# 12_-_IMX6_DDR3.net
KiCad netlist of a schematic drawn in Altium Designer
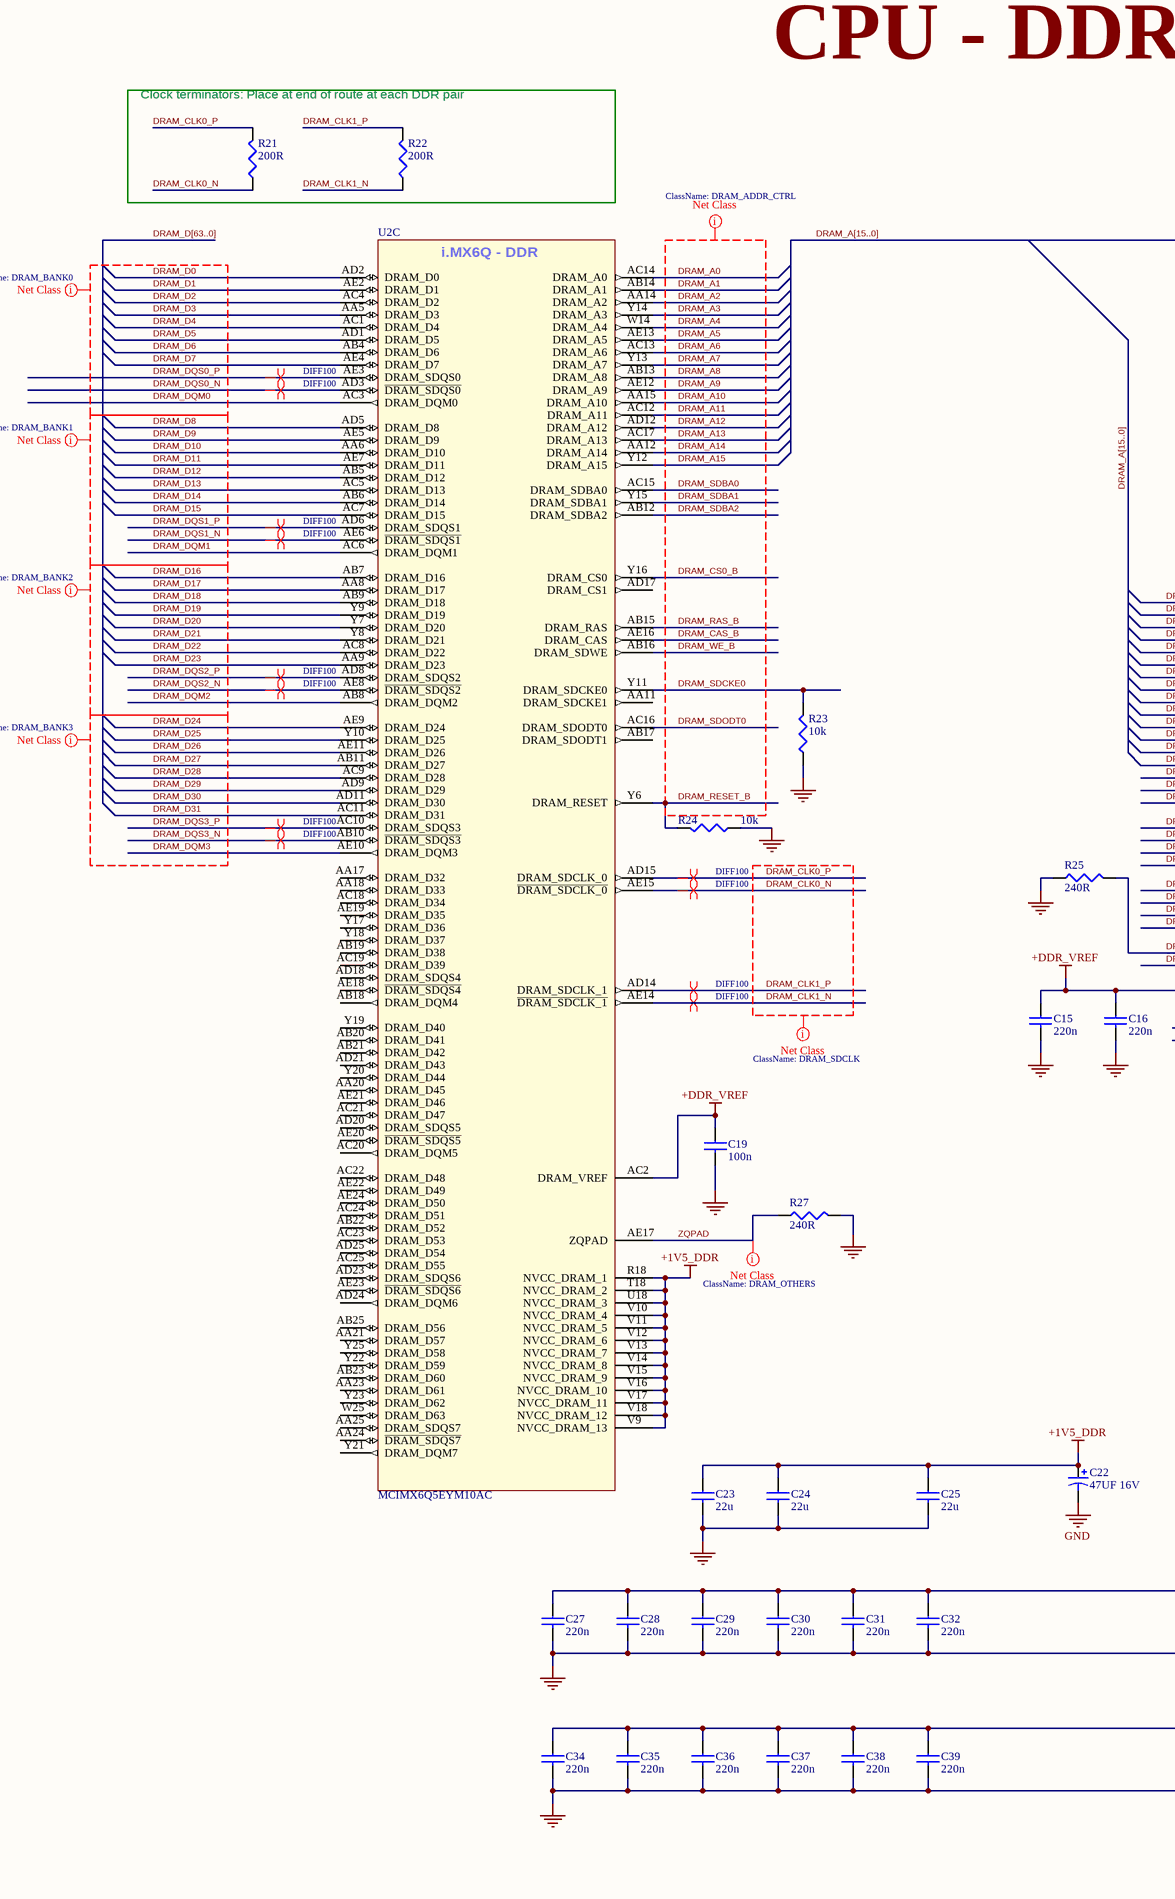
[diagram p0: [12] - IMX6_DDR3.SchDoc, left]
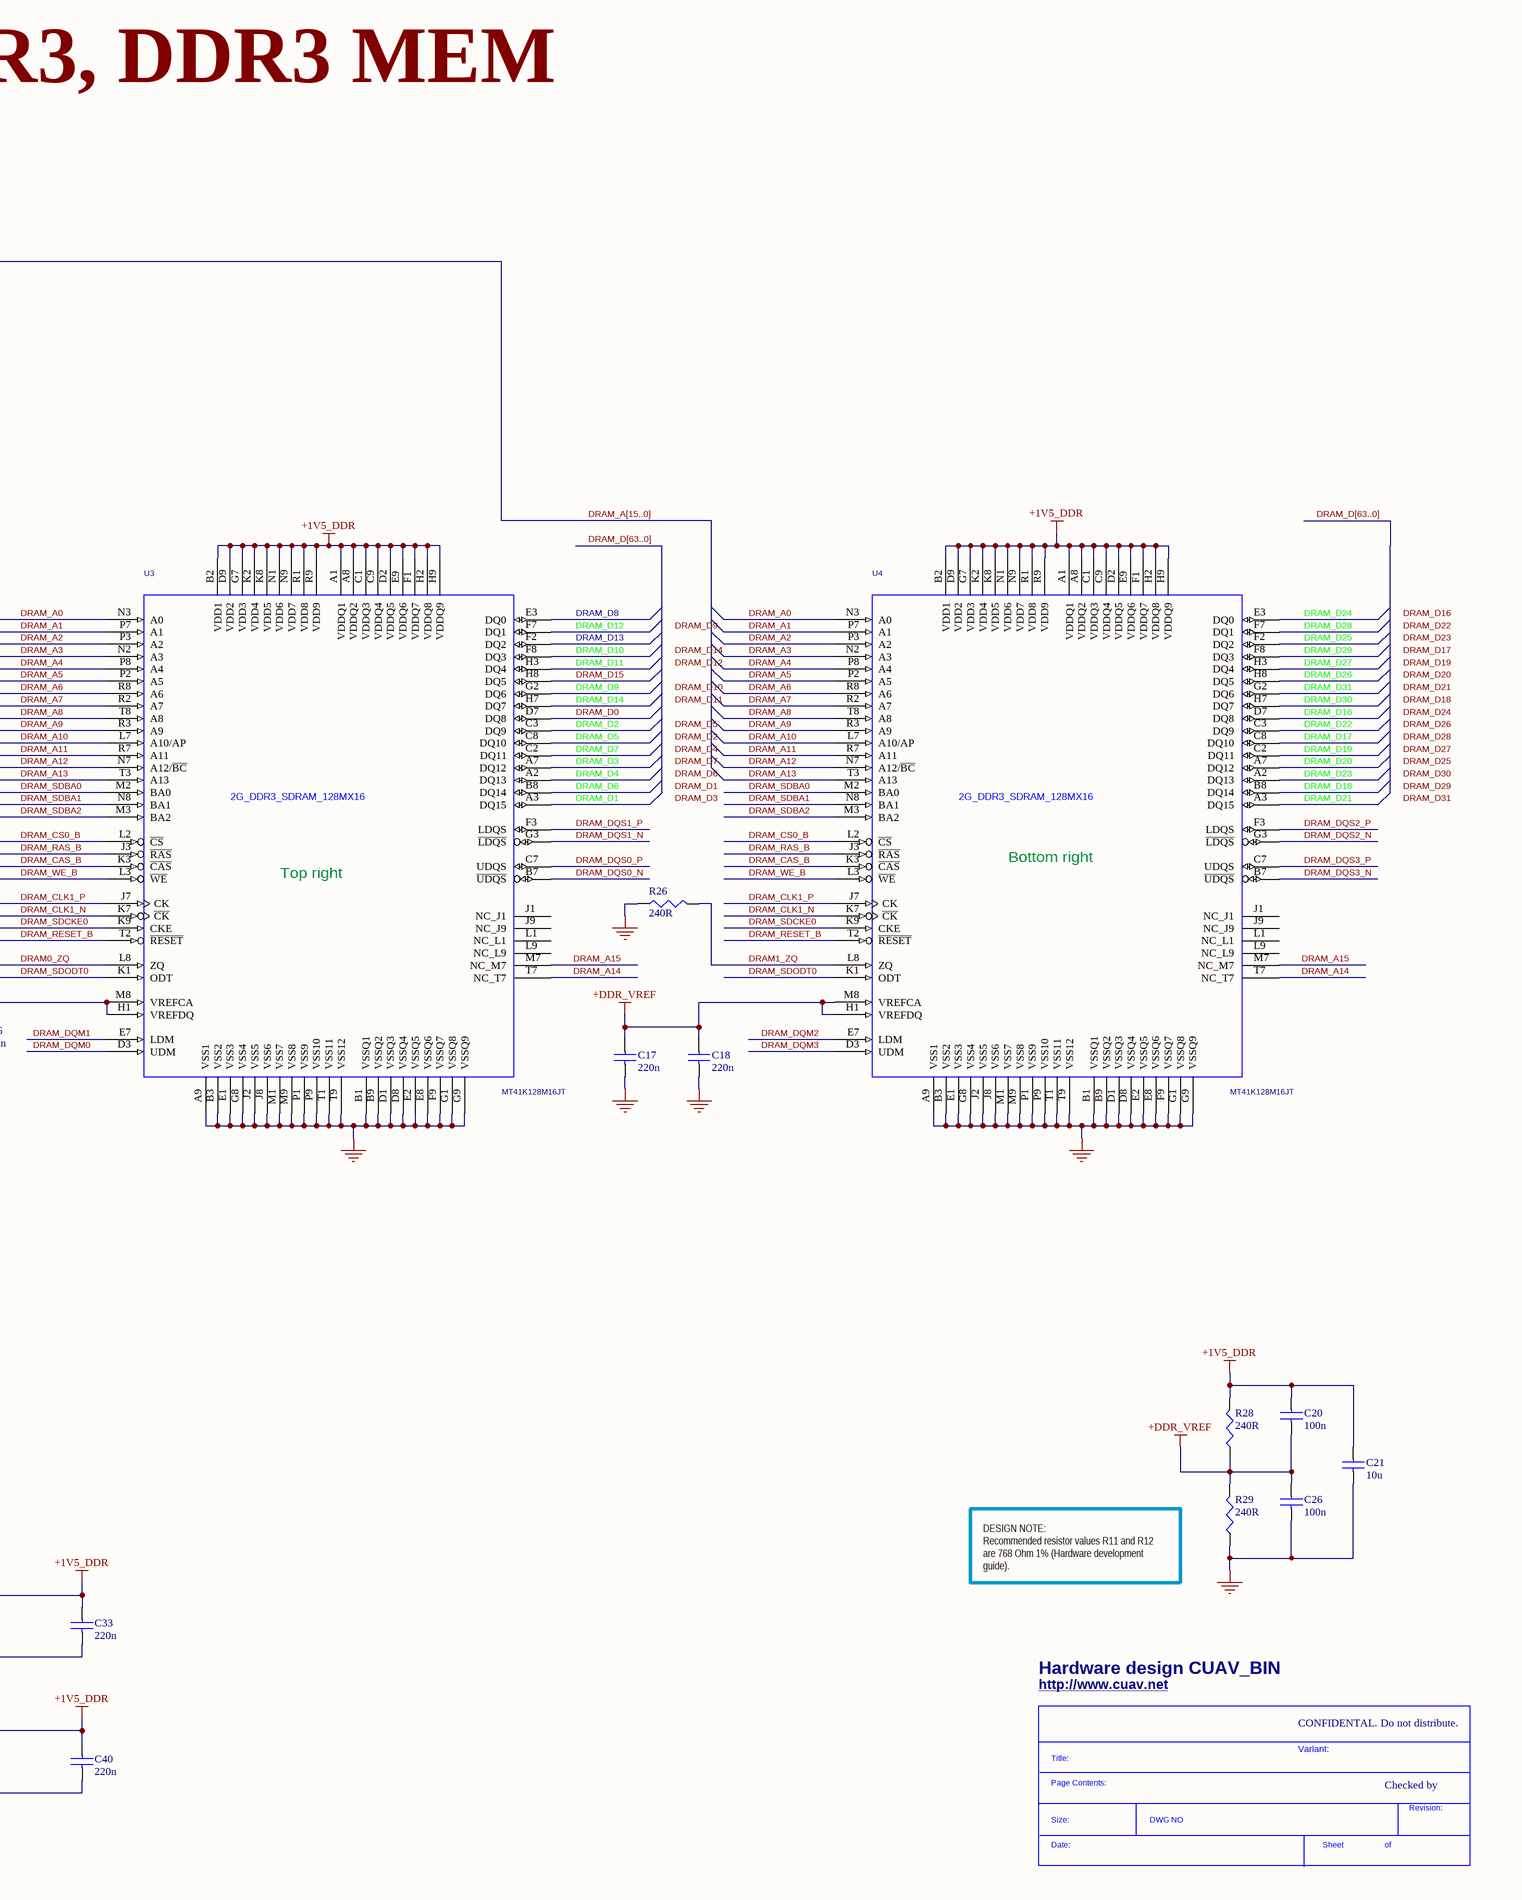
[diagram p1: [12] - IMX6_DDR3.SchDoc, right]

(export (version "E")
  (design (tool "Eeschema 10.0.6"))
  (components
    (comp (ref "*") (value "SDTitleBlock") (libsource (lib "*") (part "SDTitleBlock")))
    (comp (ref "C15")
      (value "220n")
      (footprint "0402CAP")
      (description "CAP CER .22UF 25V X5R 20% 0402")
      (fields
        (field (name "MANUFACTURER") "TDK Corporation")
        (field (name "MANUFACTURER PART NUMBER") "C1005X5R1E224M")
      )
      (libsource (lib "Integrated_Library_RF_FEB_2012") (part "C1005X5R1E224M"))
    )
    (comp (ref "C16")
      (value "220n")
      (footprint "0402CAP")
      (description "CAP CER .22UF 25V X5R 20% 0402")
      (fields
        (field (name "MANUFACTURER") "TDK Corporation")
        (field (name "MANUFACTURER PART NUMBER") "C1005X5R1E224M")
      )
      (libsource (lib "Integrated_Library_RF_FEB_2012") (part "C1005X5R1E224M"))
    )
    (comp (ref "C17")
      (value "220n")
      (footprint "0402CAP")
      (description "CAP CER .22UF 25V X5R 20% 0402")
      (fields
        (field (name "MANUFACTURER") "TDK Corporation")
        (field (name "MANUFACTURER PART NUMBER") "C1005X5R1E224M")
      )
      (libsource (lib "Integrated_Library_RF_FEB_2012") (part "C1005X5R1E224M"))
    )
    (comp (ref "C18")
      (value "220n")
      (footprint "0402CAP")
      (description "CAP CER .22UF 25V X5R 20% 0402")
      (fields
        (field (name "MANUFACTURER") "TDK Corporation")
        (field (name "MANUFACTURER PART NUMBER") "C1005X5R1E224M")
      )
      (libsource (lib "Integrated_Library_RF_FEB_2012") (part "C1005X5R1E224M"))
    )
    (comp (ref "C19")
      (value "100n")
      (footprint "C0402")
      (description "CAP CER .10UF 50V X5R 10% 0402")
      (fields
        (field (name "MANUFACTURER") "TDK Corporation")
        (field (name "MANUFACTURER PART NUMBER") "C1005X5R1H104K")
      )
      (libsource (lib "Integrated_Library_RF_FEB_2012") (part "C1005X5R1H104K"))
    )
    (comp (ref "C20")
      (value "100n")
      (footprint "0402CAP")
      (description "CAP CER .10UF 50V X5R 10% 0402")
      (fields
        (field (name "MANUFACTURER") "TDK Corporation")
        (field (name "MANUFACTURER PART NUMBER") "C1005X5R1H104K")
      )
      (libsource (lib "Integrated_Library_RF_FEB_2012") (part "C1005X5R1H104K"))
    )
    (comp (ref "C21")
      (value "10u")
      (footprint "C0603")
      (description "CAP CER 10UF 6.3V X5R 20% 0603")
      (fields
        (field (name "MANUFACTURER") "TDK Corporation")
        (field (name "MANUFACTURER PART NUMBER") "C1608X5R0J106M")
      )
      (libsource (lib "Integrated_Library_RF_FEB_2012") (part "C1608X5R0J106M"))
    )
    (comp (ref "C22")
      (value "47UF 16V")
      (footprint "7343CAP")
      (description "Polarized Capacitor (Radial)")
      (fields (field (name "PUBLISHER") "Altium Limited"))
      (libsource (lib "Miscellaneous Devices") (part "Cap Pol1"))
    )
    (comp (ref "C23")
      (value "22u")
      (footprint "C0603")
      (description "CAP CER 22UF 4V 20% X5R 0603")
      (fields
        (field (name "MANUFACTURER") "Murata Electronics North America")
        (field (name "MANUFACTURER PART NUMBER") "GRM188R60G226MEA0L")
        (field (name ".CHECKED PCB") "RF, used by MM")
        (field (name ".CHECKED SCH") "MM, checked by RF")
        (field (name ".CREATOR") "MM")
      )
      (libsource (lib "Schlib_RF") (part "GRM188R60G226MEA0L"))
    )
    (comp (ref "C24")
      (value "22u")
      (footprint "C0603")
      (description "CAP CER 22UF 4V 20% X5R 0603")
      (fields
        (field (name "MANUFACTURER") "Murata Electronics North America")
        (field (name "MANUFACTURER PART NUMBER") "GRM188R60G226MEA0L")
        (field (name ".CHECKED PCB") "RF, used by MM")
        (field (name ".CHECKED SCH") "MM, checked by RF")
        (field (name ".CREATOR") "MM")
      )
      (libsource (lib "Schlib_RF") (part "GRM188R60G226MEA0L"))
    )
    (comp (ref "C25")
      (value "22u")
      (footprint "C0603")
      (description "CAP CER 22UF 4V 20% X5R 0603")
      (fields
        (field (name "MANUFACTURER") "Murata Electronics North America")
        (field (name "MANUFACTURER PART NUMBER") "GRM188R60G226MEA0L")
        (field (name ".CHECKED PCB") "RF, used by MM")
        (field (name ".CHECKED SCH") "MM, checked by RF")
        (field (name ".CREATOR") "MM")
      )
      (libsource (lib "Schlib_RF") (part "GRM188R60G226MEA0L"))
    )
    (comp (ref "C26")
      (value "100n")
      (footprint "0402CAP")
      (description "CAP CER .10UF 50V X5R 10% 0402")
      (fields
        (field (name "MANUFACTURER") "TDK Corporation")
        (field (name "MANUFACTURER PART NUMBER") "C1005X5R1H104K")
      )
      (libsource (lib "Integrated_Library_RF_FEB_2012") (part "C1005X5R1H104K"))
    )
    (comp (ref "C27")
      (value "220n")
      (footprint "0402CAP")
      (description "CAP CER .22UF 25V X5R 20% 0402")
      (fields
        (field (name "MANUFACTURER") "TDK Corporation")
        (field (name "MANUFACTURER PART NUMBER") "C1005X5R1E224M")
      )
      (libsource (lib "Integrated_Library_RF_FEB_2012") (part "C1005X5R1E224M"))
    )
    (comp (ref "C28")
      (value "220n")
      (footprint "0402CAP")
      (description "CAP CER .22UF 25V X5R 20% 0402")
      (fields
        (field (name "MANUFACTURER") "TDK Corporation")
        (field (name "MANUFACTURER PART NUMBER") "C1005X5R1E224M")
      )
      (libsource (lib "Integrated_Library_RF_FEB_2012") (part "C1005X5R1E224M"))
    )
    (comp (ref "C29")
      (value "220n")
      (footprint "0402CAP")
      (description "CAP CER .22UF 25V X5R 20% 0402")
      (fields
        (field (name "MANUFACTURER") "TDK Corporation")
        (field (name "MANUFACTURER PART NUMBER") "C1005X5R1E224M")
      )
      (libsource (lib "Integrated_Library_RF_FEB_2012") (part "C1005X5R1E224M"))
    )
    (comp (ref "C30")
      (value "220n")
      (footprint "0402CAP")
      (description "CAP CER .22UF 25V X5R 20% 0402")
      (fields
        (field (name "MANUFACTURER") "TDK Corporation")
        (field (name "MANUFACTURER PART NUMBER") "C1005X5R1E224M")
      )
      (libsource (lib "Integrated_Library_RF_FEB_2012") (part "C1005X5R1E224M"))
    )
    (comp (ref "C31")
      (value "220n")
      (footprint "0402CAP")
      (description "CAP CER .22UF 25V X5R 20% 0402")
      (fields
        (field (name "MANUFACTURER") "TDK Corporation")
        (field (name "MANUFACTURER PART NUMBER") "C1005X5R1E224M")
      )
      (libsource (lib "Integrated_Library_RF_FEB_2012") (part "C1005X5R1E224M"))
    )
    (comp (ref "C32")
      (value "220n")
      (footprint "0402CAP")
      (description "CAP CER .22UF 25V X5R 20% 0402")
      (fields
        (field (name "MANUFACTURER") "TDK Corporation")
        (field (name "MANUFACTURER PART NUMBER") "C1005X5R1E224M")
      )
      (libsource (lib "Integrated_Library_RF_FEB_2012") (part "C1005X5R1E224M"))
    )
    (comp (ref "C33")
      (value "220n")
      (footprint "0402CAP")
      (description "CAP CER .22UF 25V X5R 20% 0402")
      (fields
        (field (name "MANUFACTURER") "TDK Corporation")
        (field (name "MANUFACTURER PART NUMBER") "C1005X5R1E224M")
      )
      (libsource (lib "Integrated_Library_RF_FEB_2012") (part "C1005X5R1E224M"))
    )
    (comp (ref "C34")
      (value "220n")
      (footprint "0402CAP")
      (description "CAP CER .22UF 25V X5R 20% 0402")
      (fields
        (field (name "MANUFACTURER") "TDK Corporation")
        (field (name "MANUFACTURER PART NUMBER") "C1005X5R1E224M")
      )
      (libsource (lib "Integrated_Library_RF_FEB_2012") (part "C1005X5R1E224M"))
    )
    (comp (ref "C35")
      (value "220n")
      (footprint "0402CAP")
      (description "CAP CER .22UF 25V X5R 20% 0402")
      (fields
        (field (name "MANUFACTURER") "TDK Corporation")
        (field (name "MANUFACTURER PART NUMBER") "C1005X5R1E224M")
      )
      (libsource (lib "Integrated_Library_RF_FEB_2012") (part "C1005X5R1E224M"))
    )
    (comp (ref "C36")
      (value "220n")
      (footprint "0402CAP")
      (description "CAP CER .22UF 25V X5R 20% 0402")
      (fields
        (field (name "MANUFACTURER") "TDK Corporation")
        (field (name "MANUFACTURER PART NUMBER") "C1005X5R1E224M")
      )
      (libsource (lib "Integrated_Library_RF_FEB_2012") (part "C1005X5R1E224M"))
    )
    (comp (ref "C37")
      (value "220n")
      (footprint "0402CAP")
      (description "CAP CER .22UF 25V X5R 20% 0402")
      (fields
        (field (name "MANUFACTURER") "TDK Corporation")
        (field (name "MANUFACTURER PART NUMBER") "C1005X5R1E224M")
      )
      (libsource (lib "Integrated_Library_RF_FEB_2012") (part "C1005X5R1E224M"))
    )
    (comp (ref "C38")
      (value "220n")
      (footprint "0402CAP")
      (description "CAP CER .22UF 25V X5R 20% 0402")
      (fields
        (field (name "MANUFACTURER") "TDK Corporation")
        (field (name "MANUFACTURER PART NUMBER") "C1005X5R1E224M")
      )
      (libsource (lib "Integrated_Library_RF_FEB_2012") (part "C1005X5R1E224M"))
    )
    (comp (ref "C39")
      (value "220n")
      (footprint "0402CAP")
      (description "CAP CER .22UF 25V X5R 20% 0402")
      (fields
        (field (name "MANUFACTURER") "TDK Corporation")
        (field (name "MANUFACTURER PART NUMBER") "C1005X5R1E224M")
      )
      (libsource (lib "Integrated_Library_RF_FEB_2012") (part "C1005X5R1E224M"))
    )
    (comp (ref "C40")
      (value "220n")
      (footprint "0402CAP")
      (description "CAP CER .22UF 25V X5R 20% 0402")
      (fields
        (field (name "MANUFACTURER") "TDK Corporation")
        (field (name "MANUFACTURER PART NUMBER") "C1005X5R1E224M")
      )
      (libsource (lib "Integrated_Library_RF_FEB_2012") (part "C1005X5R1E224M"))
    )
    (comp (ref "R21")
      (value "200R")
      (footprint "R0402")
      (description "RES 200 OHM 1/16W 1% 0402 SMD")
      (fields
        (field (name "MANUFACTURER") "Vishay Dale")
        (field (name "MANUFACTURER PART NUMBER") "CRCW0402200RFKED")
        (field (name ".CHECKED PCB") "RF, used by MM")
        (field (name ".CHECKED SCH") "MM, checked by RF")
        (field (name ".CREATOR") "MM")
      )
      (libsource (lib "Schlib_RF") (part "CRCW0402200RFKED"))
    )
    (comp (ref "R22")
      (value "200R")
      (footprint "R0402")
      (description "RES 200 OHM 1/16W 1% 0402 SMD")
      (fields
        (field (name "MANUFACTURER") "Vishay Dale")
        (field (name "MANUFACTURER PART NUMBER") "CRCW0402200RFKED")
        (field (name ".CHECKED PCB") "RF, used by MM")
        (field (name ".CHECKED SCH") "MM, checked by RF")
        (field (name ".CREATOR") "MM")
      )
      (libsource (lib "Schlib_RF") (part "CRCW0402200RFKED"))
    )
    (comp (ref "R23")
      (value "10k")
      (footprint "R0402")
      (description "RES 10.0K OHM 1/16W 1% 0402 SMD")
      (fields
        (field (name "MANUFACTURER") "Yageo")
        (field (name "MANUFACTURER PART NUMBER") "RC0402FR-0710KL")
      )
      (libsource (lib "Integrated_Library_RF_FEB_2012") (part "RC0402FR-0710KL"))
    )
    (comp (ref "R24")
      (value "10k")
      (footprint "R0402")
      (description "RES 10.0K OHM 1/16W 1% 0402 SMD")
      (fields
        (field (name "MANUFACTURER") "Yageo")
        (field (name "MANUFACTURER PART NUMBER") "RC0402FR-0710KL")
      )
      (libsource (lib "Integrated_Library_RF_FEB_2012") (part "RC0402FR-0710KL"))
    )
    (comp (ref "R25")
      (value "240R")
      (footprint "R0402")
      (description "RES TF 240 OHM 1% 0.0625W 0402")
      (fields
        (field (name "MANUFACTURER") "Stackpole Electronics Inc")
        (field (name "MANUFACTURER PART NUMBER") "RMCF0402FT240R")
      )
      (libsource (lib "Integrated_Library_RF_FEB_2012") (part "RMCF0402FT240R"))
    )
    (comp (ref "R26")
      (value "240R")
      (footprint "R0402")
      (description "RES TF 240 OHM 1% 0.0625W 0402")
      (fields
        (field (name "MANUFACTURER") "Stackpole Electronics Inc")
        (field (name "MANUFACTURER PART NUMBER") "RMCF0402FT240R")
      )
      (libsource (lib "Integrated_Library_RF_FEB_2012") (part "RMCF0402FT240R"))
    )
    (comp (ref "R27")
      (value "240R")
      (footprint "R0402")
      (description "RES TF 240 OHM 1% 0.0625W 0402")
      (fields
        (field (name "MANUFACTURER") "Stackpole Electronics Inc")
        (field (name "MANUFACTURER PART NUMBER") "RMCF0402FT240R")
      )
      (libsource (lib "Integrated_Library_RF_FEB_2012") (part "RMCF0402FT240R"))
    )
    (comp (ref "R28")
      (value "240R")
      (footprint "R0402")
      (description "RES TF 240 OHM 1% 0.0625W 0402")
      (fields
        (field (name "MANUFACTURER") "Stackpole Electronics Inc")
        (field (name "MANUFACTURER PART NUMBER") "RMCF0402FT240R")
      )
      (libsource (lib "Integrated_Library_RF_FEB_2012") (part "RMCF0402FT240R"))
    )
    (comp (ref "R29")
      (value "240R")
      (footprint "R0402")
      (description "RES TF 240 OHM 1% 0.0625W 0402")
      (fields
        (field (name "MANUFACTURER") "Stackpole Electronics Inc")
        (field (name "MANUFACTURER PART NUMBER") "RMCF0402FT240R")
      )
      (libsource (lib "Integrated_Library_RF_FEB_2012") (part "RMCF0402FT240R"))
    )
    (comp (ref "U2")
      (value "MCIMX6Q5EYM10AC")
      (footprint "PBGA624")
      (description "IC MCU 32BIT ARM QUAD 624FCBGA")
      (fields
        (field (name "MANUFACTURER") "Freescale Semiconductor")
        (field (name ".CREATOR") "MM")
        (field (name ".CHECKED PCB") "MM, checked by RF")
        (field (name ".CHECKED SCH") "MM")
      )
      (libsource (lib "Schlib_RF") (part "MCIMX6Q5EYM10AC"))
    )
    (comp (ref "U3")
      (value "MT41K128M16JT")
      (footprint "96_FPGA_DD3")
      (description "IC MEM DDR3 SDRAM 2Gb 128MX16 1.35V FBGA96")
      (libsource (lib "*") (part "2G_DDR3_SDRAM_128MX16_96P"))
    )
    (comp (ref "U4")
      (value "MT41K128M16JT")
      (footprint "96_FPGA_DD3")
      (description "IC MEM DDR3 SDRAM 2Gb 128MX16 1.35V FBGA96")
      (libsource (lib "*") (part "2G_DDR3_SDRAM_128MX16_96P"))
    )
  )
  (nets
    (net (code "33") (name "+1V5_DDR") (class "Default")
      (node (ref "C20") (pin "1") (pinfunction "1_1") (pintype "passive"))
      (node (ref "C21") (pin "1") (pinfunction "1_1") (pintype "passive"))
      (node (ref "C22") (pin "A") (pinfunction "1_A") (pintype "passive"))
      (node (ref "C23") (pin "1") (pinfunction "1_1") (pintype "passive"))
      (node (ref "C24") (pin "1") (pinfunction "1_1") (pintype "passive"))
      (node (ref "C25") (pin "1") (pinfunction "1_1") (pintype "passive"))
      (node (ref "C27") (pin "1") (pinfunction "1_1") (pintype "passive"))
      (node (ref "C28") (pin "1") (pinfunction "1_1") (pintype "passive"))
      (node (ref "C29") (pin "1") (pinfunction "1_1") (pintype "passive"))
      (node (ref "C30") (pin "1") (pinfunction "1_1") (pintype "passive"))
      (node (ref "C31") (pin "1") (pinfunction "1_1") (pintype "passive"))
      (node (ref "C32") (pin "1") (pinfunction "1_1") (pintype "passive"))
      (node (ref "C33") (pin "1") (pinfunction "1_1") (pintype "passive"))
      (node (ref "C34") (pin "1") (pinfunction "1_1") (pintype "passive"))
      (node (ref "C35") (pin "1") (pinfunction "1_1") (pintype "passive"))
      (node (ref "C36") (pin "1") (pinfunction "1_1") (pintype "passive"))
      (node (ref "C37") (pin "1") (pinfunction "1_1") (pintype "passive"))
      (node (ref "C38") (pin "1") (pinfunction "1_1") (pintype "passive"))
      (node (ref "C39") (pin "1") (pinfunction "1_1") (pintype "passive"))
      (node (ref "C40") (pin "1") (pinfunction "1_1") (pintype "passive"))
      (node (ref "R28") (pin "2") (pinfunction "2_2") (pintype "passive"))
      (node (ref "U2") (pin "R18") (pinfunction "NVCC_DRAM_1_R18") (pintype "power_in"))
      (node (ref "U2") (pin "T18") (pinfunction "NVCC_DRAM_2_T18") (pintype "power_in"))
      (node (ref "U2") (pin "U18") (pinfunction "NVCC_DRAM_3_U18") (pintype "power_in"))
      (node (ref "U2") (pin "V10") (pinfunction "NVCC_DRAM_4_V10") (pintype "power_in"))
      (node (ref "U2") (pin "V11") (pinfunction "NVCC_DRAM_5_V11") (pintype "power_in"))
      (node (ref "U2") (pin "V12") (pinfunction "NVCC_DRAM_6_V12") (pintype "power_in"))
      (node (ref "U2") (pin "V13") (pinfunction "NVCC_DRAM_7_V13") (pintype "power_in"))
      (node (ref "U2") (pin "V14") (pinfunction "NVCC_DRAM_8_V14") (pintype "power_in"))
      (node (ref "U2") (pin "V15") (pinfunction "NVCC_DRAM_9_V15") (pintype "power_in"))
      (node (ref "U2") (pin "V16") (pinfunction "NVCC_DRAM_10_V16") (pintype "power_in"))
      (node (ref "U2") (pin "V17") (pinfunction "NVCC_DRAM_11_V17") (pintype "power_in"))
      (node (ref "U2") (pin "V18") (pinfunction "NVCC_DRAM_12_V18") (pintype "power_in"))
      (node (ref "U2") (pin "V9") (pinfunction "NVCC_DRAM_13_V9") (pintype "power_in"))
      (node (ref "U3") (pin "A1") (pinfunction "VDDQ1_A1") (pintype "power_in"))
      (node (ref "U3") (pin "A8") (pinfunction "VDDQ2_A8") (pintype "power_in"))
      (node (ref "U3") (pin "B2") (pinfunction "VDD1_B2") (pintype "power_in"))
      (node (ref "U3") (pin "C1") (pinfunction "VDDQ3_C1") (pintype "power_in"))
      (node (ref "U3") (pin "C9") (pinfunction "VDDQ4_C9") (pintype "power_in"))
      (node (ref "U3") (pin "D2") (pinfunction "VDDQ5_D2") (pintype "power_in"))
      (node (ref "U3") (pin "D9") (pinfunction "VDD2_D9") (pintype "power_in"))
      (node (ref "U3") (pin "E9") (pinfunction "VDDQ6_E9") (pintype "power_in"))
      (node (ref "U3") (pin "F1") (pinfunction "VDDQ7_F1") (pintype "power_in"))
      (node (ref "U3") (pin "G7") (pinfunction "VDD3_G7") (pintype "power_in"))
      (node (ref "U3") (pin "H2") (pinfunction "VDDQ8_H2") (pintype "power_in"))
      (node (ref "U3") (pin "H9") (pinfunction "VDDQ9_H9") (pintype "power_in"))
      (node (ref "U3") (pin "K2") (pinfunction "VDD4_K2") (pintype "power_in"))
      (node (ref "U3") (pin "K8") (pinfunction "VDD5_K8") (pintype "power_in"))
      (node (ref "U3") (pin "N1") (pinfunction "VDD6_N1") (pintype "power_in"))
      (node (ref "U3") (pin "N9") (pinfunction "VDD7_N9") (pintype "power_in"))
      (node (ref "U3") (pin "R1") (pinfunction "VDD8_R1") (pintype "power_in"))
      (node (ref "U3") (pin "R9") (pinfunction "VDD9_R9") (pintype "power_in"))
      (node (ref "U4") (pin "A1") (pinfunction "VDDQ1_A1") (pintype "power_in"))
      (node (ref "U4") (pin "A8") (pinfunction "VDDQ2_A8") (pintype "power_in"))
      (node (ref "U4") (pin "B2") (pinfunction "VDD1_B2") (pintype "power_in"))
      (node (ref "U4") (pin "C1") (pinfunction "VDDQ3_C1") (pintype "power_in"))
      (node (ref "U4") (pin "C9") (pinfunction "VDDQ4_C9") (pintype "power_in"))
      (node (ref "U4") (pin "D2") (pinfunction "VDDQ5_D2") (pintype "power_in"))
      (node (ref "U4") (pin "D9") (pinfunction "VDD2_D9") (pintype "power_in"))
      (node (ref "U4") (pin "E9") (pinfunction "VDDQ6_E9") (pintype "power_in"))
      (node (ref "U4") (pin "F1") (pinfunction "VDDQ7_F1") (pintype "power_in"))
      (node (ref "U4") (pin "G7") (pinfunction "VDD3_G7") (pintype "power_in"))
      (node (ref "U4") (pin "H2") (pinfunction "VDDQ8_H2") (pintype "power_in"))
      (node (ref "U4") (pin "H9") (pinfunction "VDDQ9_H9") (pintype "power_in"))
      (node (ref "U4") (pin "K2") (pinfunction "VDD4_K2") (pintype "power_in"))
      (node (ref "U4") (pin "K8") (pinfunction "VDD5_K8") (pintype "power_in"))
      (node (ref "U4") (pin "N1") (pinfunction "VDD6_N1") (pintype "power_in"))
      (node (ref "U4") (pin "N9") (pinfunction "VDD7_N9") (pintype "power_in"))
      (node (ref "U4") (pin "R1") (pinfunction "VDD8_R1") (pintype "power_in"))
      (node (ref "U4") (pin "R9") (pinfunction "VDD9_R9") (pintype "power_in"))
    )
    (net (code "34") (name "+DDR_VREF") (class "Default")
      (node (ref "C15") (pin "1") (pinfunction "1_1") (pintype "passive"))
      (node (ref "C16") (pin "1") (pinfunction "1_1") (pintype "passive"))
      (node (ref "C17") (pin "1") (pinfunction "1_1") (pintype "passive"))
      (node (ref "C18") (pin "1") (pinfunction "1_1") (pintype "passive"))
      (node (ref "C19") (pin "1") (pinfunction "1_1") (pintype "passive"))
      (node (ref "C20") (pin "2") (pinfunction "2_2") (pintype "passive"))
      (node (ref "C26") (pin "1") (pinfunction "1_1") (pintype "passive"))
      (node (ref "R28") (pin "1") (pinfunction "1_1") (pintype "passive"))
      (node (ref "R29") (pin "2") (pinfunction "2_2") (pintype "passive"))
      (node (ref "U2") (pin "AC2") (pinfunction "DRAM_VREF_AC2") (pintype "power_in"))
      (node (ref "U3") (pin "H1") (pinfunction "VREFDQ_H1") (pintype "input"))
      (node (ref "U3") (pin "M8") (pinfunction "VREFCA_M8") (pintype "input"))
      (node (ref "U4") (pin "H1") (pinfunction "VREFDQ_H1") (pintype "input"))
      (node (ref "U4") (pin "M8") (pinfunction "VREFCA_M8") (pintype "input"))
    )
    (net (code "35") (name "/DRAM0_ZQ") (class "Default")
      (node (ref "R25") (pin "2") (pinfunction "2_2") (pintype "passive"))
      (node (ref "U3") (pin "L8") (pinfunction "ZQ_L8") (pintype "input"))
    )
    (net (code "36") (name "/DRAM1_ZQ") (class "Default")
      (node (ref "R26") (pin "2") (pinfunction "2_2") (pintype "passive"))
      (node (ref "U4") (pin "L8") (pinfunction "ZQ_L8") (pintype "input"))
    )
    (net (code "37") (name "/DRAM_A0") (class "Default")
      (node (ref "U2") (pin "AC14") (pinfunction "DRAM_A0_AC14") (pintype "output"))
      (node (ref "U3") (pin "N3") (pinfunction "A0_N3") (pintype "input"))
      (node (ref "U4") (pin "N3") (pinfunction "A0_N3") (pintype "input"))
    )
    (net (code "38") (name "/DRAM_A1") (class "Default")
      (node (ref "U2") (pin "AB14") (pinfunction "DRAM_A1_AB14") (pintype "output"))
      (node (ref "U3") (pin "P7") (pinfunction "A1_P7") (pintype "input"))
      (node (ref "U4") (pin "P7") (pinfunction "A1_P7") (pintype "input"))
    )
    (net (code "39") (name "/DRAM_A2") (class "Default")
      (node (ref "U2") (pin "AA14") (pinfunction "DRAM_A2_AA14") (pintype "output"))
      (node (ref "U3") (pin "P3") (pinfunction "A2_P3") (pintype "input"))
      (node (ref "U4") (pin "P3") (pinfunction "A2_P3") (pintype "input"))
    )
    (net (code "40") (name "/DRAM_A3") (class "Default")
      (node (ref "U2") (pin "Y14") (pinfunction "DRAM_A3_Y14") (pintype "output"))
      (node (ref "U3") (pin "N2") (pinfunction "A3_N2") (pintype "input"))
      (node (ref "U4") (pin "N2") (pinfunction "A3_N2") (pintype "input"))
    )
    (net (code "41") (name "/DRAM_A4") (class "Default")
      (node (ref "U2") (pin "W14") (pinfunction "DRAM_A4_W14") (pintype "output"))
      (node (ref "U3") (pin "P8") (pinfunction "A4_P8") (pintype "input"))
      (node (ref "U4") (pin "P8") (pinfunction "A4_P8") (pintype "input"))
    )
    (net (code "42") (name "/DRAM_A5") (class "Default")
      (node (ref "U2") (pin "AE13") (pinfunction "DRAM_A5_AE13") (pintype "output"))
      (node (ref "U3") (pin "P2") (pinfunction "A5_P2") (pintype "input"))
      (node (ref "U4") (pin "P2") (pinfunction "A5_P2") (pintype "input"))
    )
    (net (code "43") (name "/DRAM_A6") (class "Default")
      (node (ref "U2") (pin "AC13") (pinfunction "DRAM_A6_AC13") (pintype "output"))
      (node (ref "U3") (pin "R8") (pinfunction "A6_R8") (pintype "input"))
      (node (ref "U4") (pin "R8") (pinfunction "A6_R8") (pintype "input"))
    )
    (net (code "44") (name "/DRAM_A7") (class "Default")
      (node (ref "U2") (pin "Y13") (pinfunction "DRAM_A7_Y13") (pintype "output"))
      (node (ref "U3") (pin "R2") (pinfunction "A7_R2") (pintype "input"))
      (node (ref "U4") (pin "R2") (pinfunction "A7_R2") (pintype "input"))
    )
    (net (code "45") (name "/DRAM_A8") (class "Default")
      (node (ref "U2") (pin "AB13") (pinfunction "DRAM_A8_AB13") (pintype "output"))
      (node (ref "U3") (pin "T8") (pinfunction "A8_T8") (pintype "input"))
      (node (ref "U4") (pin "T8") (pinfunction "A8_T8") (pintype "input"))
    )
    (net (code "46") (name "/DRAM_A9") (class "Default")
      (node (ref "U2") (pin "AE12") (pinfunction "DRAM_A9_AE12") (pintype "output"))
      (node (ref "U3") (pin "R3") (pinfunction "A9_R3") (pintype "input"))
      (node (ref "U4") (pin "R3") (pinfunction "A9_R3") (pintype "input"))
    )
    (net (code "47") (name "/DRAM_A10") (class "Default")
      (node (ref "U2") (pin "AA15") (pinfunction "DRAM_A10_AA15") (pintype "output"))
      (node (ref "U3") (pin "L7") (pinfunction "A10/AP_L7") (pintype "input"))
      (node (ref "U4") (pin "L7") (pinfunction "A10/AP_L7") (pintype "input"))
    )
    (net (code "48") (name "/DRAM_A11") (class "Default")
      (node (ref "U2") (pin "AC12") (pinfunction "DRAM_A11_AC12") (pintype "output"))
      (node (ref "U3") (pin "R7") (pinfunction "A11_R7") (pintype "input"))
      (node (ref "U4") (pin "R7") (pinfunction "A11_R7") (pintype "input"))
    )
    (net (code "49") (name "/DRAM_A12") (class "Default")
      (node (ref "U2") (pin "AD12") (pinfunction "DRAM_A12_AD12") (pintype "output"))
      (node (ref "U3") (pin "N7") (pinfunction "A12/~{BC}_N7") (pintype "input"))
      (node (ref "U4") (pin "N7") (pinfunction "A12/~{BC}_N7") (pintype "input"))
    )
    (net (code "50") (name "/DRAM_A13") (class "Default")
      (node (ref "U2") (pin "AC17") (pinfunction "DRAM_A13_AC17") (pintype "output"))
      (node (ref "U3") (pin "T3") (pinfunction "A13_T3") (pintype "input"))
      (node (ref "U4") (pin "T3") (pinfunction "A13_T3") (pintype "input"))
    )
    (net (code "51") (name "/DRAM_A14") (class "Default")
      (node (ref "U2") (pin "AA12") (pinfunction "DRAM_A14_AA12") (pintype "output"))
      (node (ref "U3") (pin "T7") (pinfunction "NC_T7_T7") (pintype "passive"))
      (node (ref "U4") (pin "T7") (pinfunction "NC_T7_T7") (pintype "passive"))
    )
    (net (code "52") (name "/DRAM_A15") (class "Default")
      (node (ref "U2") (pin "Y12") (pinfunction "DRAM_A15_Y12") (pintype "output"))
      (node (ref "U3") (pin "M7") (pinfunction "NC_M7_M7") (pintype "passive"))
      (node (ref "U4") (pin "M7") (pinfunction "NC_M7_M7") (pintype "passive"))
    )
    (net (code "54") (name "/DRAM_CAS_B") (class "Default")
      (node (ref "U2") (pin "AE16") (pinfunction "DRAM_CAS_AE16") (pintype "output"))
      (node (ref "U3") (pin "K3") (pinfunction "~{CAS}_K3") (pintype "input"))
      (node (ref "U4") (pin "K3") (pinfunction "~{CAS}_K3") (pintype "input"))
    )
    (net (code "55") (name "/DRAM_CLK0_N") (class "Default")
      (node (ref "R21") (pin "1") (pinfunction "1_1") (pintype "passive"))
      (node (ref "U2") (pin "AE15") (pinfunction "~{DRAM_SDCLK_0}_AE15") (pintype "output"))
    )
    (net (code "56") (name "/DRAM_CLK0_P") (class "Default")
      (node (ref "R21") (pin "2") (pinfunction "2_2") (pintype "passive"))
      (node (ref "U2") (pin "AD15") (pinfunction "DRAM_SDCLK_0_AD15") (pintype "output"))
    )
    (net (code "57") (name "/DRAM_CLK1_N") (class "Default")
      (node (ref "R22") (pin "1") (pinfunction "1_1") (pintype "passive"))
      (node (ref "U2") (pin "AE14") (pinfunction "~{DRAM_SDCLK_1}_AE14") (pintype "output"))
      (node (ref "U3") (pin "K7") (pinfunction "~{CK}_K7") (pintype "input"))
      (node (ref "U4") (pin "K7") (pinfunction "~{CK}_K7") (pintype "input"))
    )
    (net (code "58") (name "/DRAM_CLK1_P") (class "Default")
      (node (ref "R22") (pin "2") (pinfunction "2_2") (pintype "passive"))
      (node (ref "U2") (pin "AD14") (pinfunction "DRAM_SDCLK_1_AD14") (pintype "output"))
      (node (ref "U3") (pin "J7") (pinfunction "CK_J7") (pintype "input"))
      (node (ref "U4") (pin "J7") (pinfunction "CK_J7") (pintype "input"))
    )
    (net (code "59") (name "/DRAM_CS0_B") (class "Default")
      (node (ref "U2") (pin "Y16") (pinfunction "DRAM_CS0_Y16") (pintype "output"))
      (node (ref "U3") (pin "L2") (pinfunction "~{CS}_L2") (pintype "input"))
      (node (ref "U4") (pin "L2") (pinfunction "~{CS}_L2") (pintype "input"))
    )
    (net (code "60") (name "/DRAM_D0") (class "Default")
      (node (ref "U2") (pin "AD2") (pinfunction "DRAM_D0_AD2") (pintype "bidirectional"))
      (node (ref "U3") (pin "D7") (pinfunction "DQ8_D7") (pintype "bidirectional"))
    )
    (net (code "61") (name "/DRAM_D1") (class "Default")
      (node (ref "U2") (pin "AE2") (pinfunction "DRAM_D1_AE2") (pintype "bidirectional"))
      (node (ref "U3") (pin "A3") (pinfunction "DQ15_A3") (pintype "bidirectional"))
    )
    (net (code "62") (name "/DRAM_D2") (class "Default")
      (node (ref "U2") (pin "AC4") (pinfunction "DRAM_D2_AC4") (pintype "bidirectional"))
      (node (ref "U3") (pin "C3") (pinfunction "DQ9_C3") (pintype "bidirectional"))
    )
    (net (code "63") (name "/DRAM_D3") (class "Default")
      (node (ref "U2") (pin "AA5") (pinfunction "DRAM_D3_AA5") (pintype "bidirectional"))
      (node (ref "U3") (pin "A7") (pinfunction "DQ12_A7") (pintype "bidirectional"))
    )
    (net (code "64") (name "/DRAM_D4") (class "Default")
      (node (ref "U2") (pin "AC1") (pinfunction "DRAM_D4_AC1") (pintype "bidirectional"))
      (node (ref "U3") (pin "A2") (pinfunction "DQ13_A2") (pintype "bidirectional"))
    )
    (net (code "65") (name "/DRAM_D5") (class "Default")
      (node (ref "U2") (pin "AD1") (pinfunction "DRAM_D5_AD1") (pintype "bidirectional"))
      (node (ref "U3") (pin "C8") (pinfunction "DQ10_C8") (pintype "bidirectional"))
    )
    (net (code "66") (name "/DRAM_D6") (class "Default")
      (node (ref "U2") (pin "AB4") (pinfunction "DRAM_D6_AB4") (pintype "bidirectional"))
      (node (ref "U3") (pin "B8") (pinfunction "DQ14_B8") (pintype "bidirectional"))
    )
    (net (code "67") (name "/DRAM_D7") (class "Default")
      (node (ref "U2") (pin "AE4") (pinfunction "DRAM_D7_AE4") (pintype "bidirectional"))
      (node (ref "U3") (pin "C2") (pinfunction "DQ11_C2") (pintype "bidirectional"))
    )
    (net (code "68") (name "/DRAM_D8") (class "Default")
      (node (ref "U2") (pin "AD5") (pinfunction "DRAM_D8_AD5") (pintype "bidirectional"))
      (node (ref "U3") (pin "E3") (pinfunction "DQ0_E3") (pintype "bidirectional"))
    )
    (net (code "69") (name "/DRAM_D9") (class "Default")
      (node (ref "U2") (pin "AE5") (pinfunction "DRAM_D9_AE5") (pintype "bidirectional"))
      (node (ref "U3") (pin "G2") (pinfunction "DQ6_G2") (pintype "bidirectional"))
    )
    (net (code "70") (name "/DRAM_D10") (class "Default")
      (node (ref "U2") (pin "AA6") (pinfunction "DRAM_D10_AA6") (pintype "bidirectional"))
      (node (ref "U3") (pin "F8") (pinfunction "DQ3_F8") (pintype "bidirectional"))
    )
    (net (code "71") (name "/DRAM_D11") (class "Default")
      (node (ref "U2") (pin "AE7") (pinfunction "DRAM_D11_AE7") (pintype "bidirectional"))
      (node (ref "U3") (pin "H3") (pinfunction "DQ4_H3") (pintype "bidirectional"))
    )
    (net (code "72") (name "/DRAM_D12") (class "Default")
      (node (ref "U2") (pin "AB5") (pinfunction "DRAM_D12_AB5") (pintype "bidirectional"))
      (node (ref "U3") (pin "F7") (pinfunction "DQ1_F7") (pintype "bidirectional"))
    )
    (net (code "73") (name "/DRAM_D13") (class "Default")
      (node (ref "U2") (pin "AC5") (pinfunction "DRAM_D13_AC5") (pintype "bidirectional"))
      (node (ref "U3") (pin "F2") (pinfunction "DQ2_F2") (pintype "bidirectional"))
    )
    (net (code "74") (name "/DRAM_D14") (class "Default")
      (node (ref "U2") (pin "AB6") (pinfunction "DRAM_D14_AB6") (pintype "bidirectional"))
      (node (ref "U3") (pin "H7") (pinfunction "DQ7_H7") (pintype "bidirectional"))
    )
    (net (code "75") (name "/DRAM_D15") (class "Default")
      (node (ref "U2") (pin "AC7") (pinfunction "DRAM_D15_AC7") (pintype "bidirectional"))
      (node (ref "U3") (pin "H8") (pinfunction "DQ5_H8") (pintype "bidirectional"))
    )
    (net (code "76") (name "/DRAM_D16") (class "Default")
      (node (ref "U2") (pin "AB7") (pinfunction "DRAM_D16_AB7") (pintype "bidirectional"))
      (node (ref "U4") (pin "D7") (pinfunction "DQ8_D7") (pintype "bidirectional"))
    )
    (net (code "77") (name "/DRAM_D17") (class "Default")
      (node (ref "U2") (pin "AA8") (pinfunction "DRAM_D17_AA8") (pintype "bidirectional"))
      (node (ref "U4") (pin "C8") (pinfunction "DQ10_C8") (pintype "bidirectional"))
    )
    (net (code "78") (name "/DRAM_D18") (class "Default")
      (node (ref "U2") (pin "AB9") (pinfunction "DRAM_D18_AB9") (pintype "bidirectional"))
      (node (ref "U4") (pin "B8") (pinfunction "DQ14_B8") (pintype "bidirectional"))
    )
    (net (code "79") (name "/DRAM_D19") (class "Default")
      (node (ref "U2") (pin "Y9") (pinfunction "DRAM_D19_Y9") (pintype "bidirectional"))
      (node (ref "U4") (pin "C2") (pinfunction "DQ11_C2") (pintype "bidirectional"))
    )
    (net (code "80") (name "/DRAM_D20") (class "Default")
      (node (ref "U2") (pin "Y7") (pinfunction "DRAM_D20_Y7") (pintype "bidirectional"))
      (node (ref "U4") (pin "A7") (pinfunction "DQ12_A7") (pintype "bidirectional"))
    )
    (net (code "81") (name "/DRAM_D21") (class "Default")
      (node (ref "U2") (pin "Y8") (pinfunction "DRAM_D21_Y8") (pintype "bidirectional"))
      (node (ref "U4") (pin "A3") (pinfunction "DQ15_A3") (pintype "bidirectional"))
    )
    (net (code "82") (name "/DRAM_D22") (class "Default")
      (node (ref "U2") (pin "AC8") (pinfunction "DRAM_D22_AC8") (pintype "bidirectional"))
      (node (ref "U4") (pin "C3") (pinfunction "DQ9_C3") (pintype "bidirectional"))
    )
    (net (code "83") (name "/DRAM_D23") (class "Default")
      (node (ref "U2") (pin "AA9") (pinfunction "DRAM_D23_AA9") (pintype "bidirectional"))
      (node (ref "U4") (pin "A2") (pinfunction "DQ13_A2") (pintype "bidirectional"))
    )
    (net (code "84") (name "/DRAM_D24") (class "Default")
      (node (ref "U2") (pin "AE9") (pinfunction "DRAM_D24_AE9") (pintype "bidirectional"))
      (node (ref "U4") (pin "E3") (pinfunction "DQ0_E3") (pintype "bidirectional"))
    )
    (net (code "85") (name "/DRAM_D25") (class "Default")
      (node (ref "U2") (pin "Y10") (pinfunction "DRAM_D25_Y10") (pintype "bidirectional"))
      (node (ref "U4") (pin "F2") (pinfunction "DQ2_F2") (pintype "bidirectional"))
    )
    (net (code "86") (name "/DRAM_D26") (class "Default")
      (node (ref "U2") (pin "AE11") (pinfunction "DRAM_D26_AE11") (pintype "bidirectional"))
      (node (ref "U4") (pin "H8") (pinfunction "DQ5_H8") (pintype "bidirectional"))
    )
    (net (code "87") (name "/DRAM_D27") (class "Default")
      (node (ref "U2") (pin "AB11") (pinfunction "DRAM_D27_AB11") (pintype "bidirectional"))
      (node (ref "U4") (pin "H3") (pinfunction "DQ4_H3") (pintype "bidirectional"))
    )
    (net (code "88") (name "/DRAM_D28") (class "Default")
      (node (ref "U2") (pin "AC9") (pinfunction "DRAM_D28_AC9") (pintype "bidirectional"))
      (node (ref "U4") (pin "F7") (pinfunction "DQ1_F7") (pintype "bidirectional"))
    )
    (net (code "89") (name "/DRAM_D29") (class "Default")
      (node (ref "U2") (pin "AD9") (pinfunction "DRAM_D29_AD9") (pintype "bidirectional"))
      (node (ref "U4") (pin "F8") (pinfunction "DQ3_F8") (pintype "bidirectional"))
    )
    (net (code "90") (name "/DRAM_D30") (class "Default")
      (node (ref "U2") (pin "AD11") (pinfunction "DRAM_D30_AD11") (pintype "bidirectional"))
      (node (ref "U4") (pin "H7") (pinfunction "DQ7_H7") (pintype "bidirectional"))
    )
    (net (code "91") (name "/DRAM_D31") (class "Default")
      (node (ref "U2") (pin "AC11") (pinfunction "DRAM_D31_AC11") (pintype "bidirectional"))
      (node (ref "U4") (pin "G2") (pinfunction "DQ6_G2") (pintype "bidirectional"))
    )
    (net (code "92") (name "/DRAM_DQM0") (class "Default")
      (node (ref "U2") (pin "AC3") (pinfunction "DRAM_DQM0_AC3") (pintype "output"))
      (node (ref "U3") (pin "D3") (pinfunction "UDM_D3") (pintype "input"))
    )
    (net (code "93") (name "/DRAM_DQM1") (class "Default")
      (node (ref "U2") (pin "AC6") (pinfunction "DRAM_DQM1_AC6") (pintype "output"))
      (node (ref "U3") (pin "E7") (pinfunction "LDM_E7") (pintype "input"))
    )
    (net (code "94") (name "/DRAM_DQM2") (class "Default")
      (node (ref "U2") (pin "AB8") (pinfunction "DRAM_DQM2_AB8") (pintype "output"))
      (node (ref "U4") (pin "E7") (pinfunction "LDM_E7") (pintype "input"))
    )
    (net (code "95") (name "/DRAM_DQM3") (class "Default")
      (node (ref "U2") (pin "AE10") (pinfunction "DRAM_DQM3_AE10") (pintype "output"))
      (node (ref "U4") (pin "D3") (pinfunction "UDM_D3") (pintype "input"))
    )
    (net (code "96") (name "/DRAM_DQS0_N") (class "Default")
      (node (ref "U2") (pin "AD3") (pinfunction "~{DRAM_SDQS0}_AD3") (pintype "bidirectional"))
      (node (ref "U3") (pin "B7") (pinfunction "~{UDQS}_B7") (pintype "bidirectional"))
    )
    (net (code "97") (name "/DRAM_DQS0_P") (class "Default")
      (node (ref "U2") (pin "AE3") (pinfunction "DRAM_SDQS0_AE3") (pintype "bidirectional"))
      (node (ref "U3") (pin "C7") (pinfunction "UDQS_C7") (pintype "bidirectional"))
    )
    (net (code "98") (name "/DRAM_DQS1_N") (class "Default")
      (node (ref "U2") (pin "AE6") (pinfunction "~{DRAM_SDQS1}_AE6") (pintype "bidirectional"))
      (node (ref "U3") (pin "G3") (pinfunction "~{LDQS}_G3") (pintype "bidirectional"))
    )
    (net (code "99") (name "/DRAM_DQS1_P") (class "Default")
      (node (ref "U2") (pin "AD6") (pinfunction "DRAM_SDQS1_AD6") (pintype "bidirectional"))
      (node (ref "U3") (pin "F3") (pinfunction "LDQS_F3") (pintype "bidirectional"))
    )
    (net (code "100") (name "/DRAM_DQS2_N") (class "Default")
      (node (ref "U2") (pin "AE8") (pinfunction "~{DRAM_SDQS2}_AE8") (pintype "bidirectional"))
      (node (ref "U4") (pin "G3") (pinfunction "~{LDQS}_G3") (pintype "bidirectional"))
    )
    (net (code "101") (name "/DRAM_DQS2_P") (class "Default")
      (node (ref "U2") (pin "AD8") (pinfunction "DRAM_SDQS2_AD8") (pintype "bidirectional"))
      (node (ref "U4") (pin "F3") (pinfunction "LDQS_F3") (pintype "bidirectional"))
    )
    (net (code "102") (name "/DRAM_DQS3_N") (class "Default")
      (node (ref "U2") (pin "AB10") (pinfunction "~{DRAM_SDQS3}_AB10") (pintype "bidirectional"))
      (node (ref "U4") (pin "B7") (pinfunction "~{UDQS}_B7") (pintype "bidirectional"))
    )
    (net (code "103") (name "/DRAM_DQS3_P") (class "Default")
      (node (ref "U2") (pin "AC10") (pinfunction "DRAM_SDQS3_AC10") (pintype "bidirectional"))
      (node (ref "U4") (pin "C7") (pinfunction "UDQS_C7") (pintype "bidirectional"))
    )
    (net (code "105") (name "/DRAM_RAS_B") (class "Default")
      (node (ref "U2") (pin "AB15") (pinfunction "DRAM_RAS_AB15") (pintype "output"))
      (node (ref "U3") (pin "J3") (pinfunction "~{RAS}_J3") (pintype "input"))
      (node (ref "U4") (pin "J3") (pinfunction "~{RAS}_J3") (pintype "input"))
    )
    (net (code "106") (name "/DRAM_RESET_B") (class "Default")
      (node (ref "R24") (pin "2") (pinfunction "2_2") (pintype "passive"))
      (node (ref "U2") (pin "Y6") (pinfunction "DRAM_RESET_Y6") (pintype "output"))
      (node (ref "U3") (pin "T2") (pinfunction "~{RESET}_T2") (pintype "input"))
      (node (ref "U4") (pin "T2") (pinfunction "~{RESET}_T2") (pintype "input"))
    )
    (net (code "107") (name "/DRAM_SDBA0") (class "Default")
      (node (ref "U2") (pin "AC15") (pinfunction "DRAM_SDBA0_AC15") (pintype "output"))
      (node (ref "U3") (pin "M2") (pinfunction "BA0_M2") (pintype "input"))
      (node (ref "U4") (pin "M2") (pinfunction "BA0_M2") (pintype "input"))
    )
    (net (code "108") (name "/DRAM_SDBA1") (class "Default")
      (node (ref "U2") (pin "Y15") (pinfunction "DRAM_SDBA1_Y15") (pintype "output"))
      (node (ref "U3") (pin "N8") (pinfunction "BA1_N8") (pintype "input"))
      (node (ref "U4") (pin "N8") (pinfunction "BA1_N8") (pintype "input"))
    )
    (net (code "109") (name "/DRAM_SDBA2") (class "Default")
      (node (ref "U2") (pin "AB12") (pinfunction "DRAM_SDBA2_AB12") (pintype "output"))
      (node (ref "U3") (pin "M3") (pinfunction "BA2_M3") (pintype "input"))
      (node (ref "U4") (pin "M3") (pinfunction "BA2_M3") (pintype "input"))
    )
    (net (code "110") (name "/DRAM_SDCKE0") (class "Default")
      (node (ref "R23") (pin "2") (pinfunction "2_2") (pintype "passive"))
      (node (ref "U2") (pin "Y11") (pinfunction "DRAM_SDCKE0_Y11") (pintype "output"))
      (node (ref "U3") (pin "K9") (pinfunction "CKE_K9") (pintype "input"))
      (node (ref "U4") (pin "K9") (pinfunction "CKE_K9") (pintype "input"))
    )
    (net (code "111") (name "/DRAM_SDODT0") (class "Default")
      (node (ref "U2") (pin "AC16") (pinfunction "DRAM_SDODT0_AC16") (pintype "output"))
      (node (ref "U3") (pin "K1") (pinfunction "ODT_K1") (pintype "input"))
      (node (ref "U4") (pin "K1") (pinfunction "ODT_K1") (pintype "input"))
    )
    (net (code "112") (name "/DRAM_WE_B") (class "Default")
      (node (ref "U2") (pin "AB16") (pinfunction "DRAM_SDWE_AB16") (pintype "output"))
      (node (ref "U3") (pin "L3") (pinfunction "~{WE}_L3") (pintype "input"))
      (node (ref "U4") (pin "L3") (pinfunction "~{WE}_L3") (pintype "input"))
    )
    (net (code "113") (name "/ZQPAD") (class "Default")
      (node (ref "R27") (pin "1") (pinfunction "1_1") (pintype "passive"))
      (node (ref "U2") (pin "AE17") (pinfunction "ZQPAD_AE17") (pintype "passive"))
    )
    (net (code "114") (name "GND") (class "Default")
      (node (ref "C15") (pin "2") (pinfunction "2_2") (pintype "passive"))
      (node (ref "C16") (pin "2") (pinfunction "2_2") (pintype "passive"))
      (node (ref "C17") (pin "2") (pinfunction "2_2") (pintype "passive"))
      (node (ref "C18") (pin "2") (pinfunction "2_2") (pintype "passive"))
      (node (ref "C19") (pin "2") (pinfunction "2_2") (pintype "passive"))
      (node (ref "C21") (pin "2") (pinfunction "2_2") (pintype "passive"))
      (node (ref "C22") (pin "C") (pinfunction "2_C") (pintype "passive"))
      (node (ref "C23") (pin "2") (pinfunction "2_2") (pintype "passive"))
      (node (ref "C24") (pin "2") (pinfunction "2_2") (pintype "passive"))
      (node (ref "C25") (pin "2") (pinfunction "2_2") (pintype "passive"))
      (node (ref "C26") (pin "2") (pinfunction "2_2") (pintype "passive"))
      (node (ref "C27") (pin "2") (pinfunction "2_2") (pintype "passive"))
      (node (ref "C28") (pin "2") (pinfunction "2_2") (pintype "passive"))
      (node (ref "C29") (pin "2") (pinfunction "2_2") (pintype "passive"))
      (node (ref "C30") (pin "2") (pinfunction "2_2") (pintype "passive"))
      (node (ref "C31") (pin "2") (pinfunction "2_2") (pintype "passive"))
      (node (ref "C32") (pin "2") (pinfunction "2_2") (pintype "passive"))
      (node (ref "C33") (pin "2") (pinfunction "2_2") (pintype "passive"))
      (node (ref "C34") (pin "2") (pinfunction "2_2") (pintype "passive"))
      (node (ref "C35") (pin "2") (pinfunction "2_2") (pintype "passive"))
      (node (ref "C36") (pin "2") (pinfunction "2_2") (pintype "passive"))
      (node (ref "C37") (pin "2") (pinfunction "2_2") (pintype "passive"))
      (node (ref "C38") (pin "2") (pinfunction "2_2") (pintype "passive"))
      (node (ref "C39") (pin "2") (pinfunction "2_2") (pintype "passive"))
      (node (ref "C40") (pin "2") (pinfunction "2_2") (pintype "passive"))
      (node (ref "R23") (pin "1") (pinfunction "1_1") (pintype "passive"))
      (node (ref "R24") (pin "1") (pinfunction "1_1") (pintype "passive"))
      (node (ref "R25") (pin "1") (pinfunction "1_1") (pintype "passive"))
      (node (ref "R26") (pin "1") (pinfunction "1_1") (pintype "passive"))
      (node (ref "R27") (pin "2") (pinfunction "2_2") (pintype "passive"))
      (node (ref "R29") (pin "1") (pinfunction "1_1") (pintype "passive"))
      (node (ref "U3") (pin "A9") (pinfunction "VSS1_A9") (pintype "power_in"))
      (node (ref "U3") (pin "B1") (pinfunction "VSSQ1_B1") (pintype "power_in"))
      (node (ref "U3") (pin "B3") (pinfunction "VSS2_B3") (pintype "power_in"))
      (node (ref "U3") (pin "B9") (pinfunction "VSSQ2_B9") (pintype "power_in"))
      (node (ref "U3") (pin "D1") (pinfunction "VSSQ3_D1") (pintype "power_in"))
      (node (ref "U3") (pin "D8") (pinfunction "VSSQ4_D8") (pintype "power_in"))
      (node (ref "U3") (pin "E1") (pinfunction "VSS3_E1") (pintype "power_in"))
      (node (ref "U3") (pin "E2") (pinfunction "VSSQ5_E2") (pintype "power_in"))
      (node (ref "U3") (pin "E8") (pinfunction "VSSQ6_E8") (pintype "power_in"))
      (node (ref "U3") (pin "F9") (pinfunction "VSSQ7_F9") (pintype "power_in"))
      (node (ref "U3") (pin "G1") (pinfunction "VSSQ8_G1") (pintype "power_in"))
      (node (ref "U3") (pin "G8") (pinfunction "VSS4_G8") (pintype "power_in"))
      (node (ref "U3") (pin "G9") (pinfunction "VSSQ9_G9") (pintype "power_in"))
      (node (ref "U3") (pin "J2") (pinfunction "VSS5_J2") (pintype "power_in"))
      (node (ref "U3") (pin "J8") (pinfunction "VSS6_J8") (pintype "power_in"))
      (node (ref "U3") (pin "M1") (pinfunction "VSS7_M1") (pintype "power_in"))
      (node (ref "U3") (pin "M9") (pinfunction "VSS8_M9") (pintype "power_in"))
      (node (ref "U3") (pin "P1") (pinfunction "VSS9_P1") (pintype "power_in"))
      (node (ref "U3") (pin "P9") (pinfunction "VSS10_P9") (pintype "power_in"))
      (node (ref "U3") (pin "T1") (pinfunction "VSS11_T1") (pintype "power_in"))
      (node (ref "U3") (pin "T9") (pinfunction "VSS12_T9") (pintype "power_in"))
      (node (ref "U4") (pin "A9") (pinfunction "VSS1_A9") (pintype "power_in"))
      (node (ref "U4") (pin "B1") (pinfunction "VSSQ1_B1") (pintype "power_in"))
      (node (ref "U4") (pin "B3") (pinfunction "VSS2_B3") (pintype "power_in"))
      (node (ref "U4") (pin "B9") (pinfunction "VSSQ2_B9") (pintype "power_in"))
      (node (ref "U4") (pin "D1") (pinfunction "VSSQ3_D1") (pintype "power_in"))
      (node (ref "U4") (pin "D8") (pinfunction "VSSQ4_D8") (pintype "power_in"))
      (node (ref "U4") (pin "E1") (pinfunction "VSS3_E1") (pintype "power_in"))
      (node (ref "U4") (pin "E2") (pinfunction "VSSQ5_E2") (pintype "power_in"))
      (node (ref "U4") (pin "E8") (pinfunction "VSSQ6_E8") (pintype "power_in"))
      (node (ref "U4") (pin "F9") (pinfunction "VSSQ7_F9") (pintype "power_in"))
      (node (ref "U4") (pin "G1") (pinfunction "VSSQ8_G1") (pintype "power_in"))
      (node (ref "U4") (pin "G8") (pinfunction "VSS4_G8") (pintype "power_in"))
      (node (ref "U4") (pin "G9") (pinfunction "VSSQ9_G9") (pintype "power_in"))
      (node (ref "U4") (pin "J2") (pinfunction "VSS5_J2") (pintype "power_in"))
      (node (ref "U4") (pin "J8") (pinfunction "VSS6_J8") (pintype "power_in"))
      (node (ref "U4") (pin "M1") (pinfunction "VSS7_M1") (pintype "power_in"))
      (node (ref "U4") (pin "M9") (pinfunction "VSS8_M9") (pintype "power_in"))
      (node (ref "U4") (pin "P1") (pinfunction "VSS9_P1") (pintype "power_in"))
      (node (ref "U4") (pin "P9") (pinfunction "VSS10_P9") (pintype "power_in"))
      (node (ref "U4") (pin "T1") (pinfunction "VSS11_T1") (pintype "power_in"))
      (node (ref "U4") (pin "T9") (pinfunction "VSS12_T9") (pintype "power_in"))
    )
    (net (code "115") (name "unconnected-(U2C-DRAM_CS1-PadAD17)") (class "Default")
      (node (ref "U2") (pin "AD17") (pinfunction "DRAM_CS1_AD17") (pintype "output"))
    )
    (net (code "116") (name "unconnected-(U2C-DRAM_D32-PadAA17)") (class "Default")
      (node (ref "U2") (pin "AA17") (pinfunction "DRAM_D32_AA17") (pintype "bidirectional"))
    )
    (net (code "117") (name "unconnected-(U2C-DRAM_D33-PadAA18)") (class "Default")
      (node (ref "U2") (pin "AA18") (pinfunction "DRAM_D33_AA18") (pintype "bidirectional"))
    )
    (net (code "118") (name "unconnected-(U2C-DRAM_D34-PadAC18)") (class "Default")
      (node (ref "U2") (pin "AC18") (pinfunction "DRAM_D34_AC18") (pintype "bidirectional"))
    )
    (net (code "119") (name "unconnected-(U2C-DRAM_D35-PadAE19)") (class "Default")
      (node (ref "U2") (pin "AE19") (pinfunction "DRAM_D35_AE19") (pintype "bidirectional"))
    )
    (net (code "120") (name "unconnected-(U2C-DRAM_D36-PadY17)") (class "Default")
      (node (ref "U2") (pin "Y17") (pinfunction "DRAM_D36_Y17") (pintype "bidirectional"))
    )
    (net (code "121") (name "unconnected-(U2C-DRAM_D37-PadY18)") (class "Default")
      (node (ref "U2") (pin "Y18") (pinfunction "DRAM_D37_Y18") (pintype "bidirectional"))
    )
    (net (code "122") (name "unconnected-(U2C-DRAM_D38-PadAB19)") (class "Default")
      (node (ref "U2") (pin "AB19") (pinfunction "DRAM_D38_AB19") (pintype "bidirectional"))
    )
    (net (code "123") (name "unconnected-(U2C-DRAM_D39-PadAC19)") (class "Default")
      (node (ref "U2") (pin "AC19") (pinfunction "DRAM_D39_AC19") (pintype "bidirectional"))
    )
    (net (code "124") (name "unconnected-(U2C-DRAM_D40-PadY19)") (class "Default")
      (node (ref "U2") (pin "Y19") (pinfunction "DRAM_D40_Y19") (pintype "bidirectional"))
    )
    (net (code "125") (name "unconnected-(U2C-DRAM_D41-PadAB20)") (class "Default")
      (node (ref "U2") (pin "AB20") (pinfunction "DRAM_D41_AB20") (pintype "bidirectional"))
    )
    (net (code "126") (name "unconnected-(U2C-DRAM_D42-PadAB21)") (class "Default")
      (node (ref "U2") (pin "AB21") (pinfunction "DRAM_D42_AB21") (pintype "bidirectional"))
    )
    (net (code "127") (name "unconnected-(U2C-DRAM_D43-PadAD21)") (class "Default")
      (node (ref "U2") (pin "AD21") (pinfunction "DRAM_D43_AD21") (pintype "bidirectional"))
    )
    (net (code "128") (name "unconnected-(U2C-DRAM_D44-PadY20)") (class "Default")
      (node (ref "U2") (pin "Y20") (pinfunction "DRAM_D44_Y20") (pintype "bidirectional"))
    )
    (net (code "129") (name "unconnected-(U2C-DRAM_D45-PadAA20)") (class "Default")
      (node (ref "U2") (pin "AA20") (pinfunction "DRAM_D45_AA20") (pintype "bidirectional"))
    )
    (net (code "130") (name "unconnected-(U2C-DRAM_D46-PadAE21)") (class "Default")
      (node (ref "U2") (pin "AE21") (pinfunction "DRAM_D46_AE21") (pintype "bidirectional"))
    )
    (net (code "131") (name "unconnected-(U2C-DRAM_D47-PadAC21)") (class "Default")
      (node (ref "U2") (pin "AC21") (pinfunction "DRAM_D47_AC21") (pintype "bidirectional"))
    )
    (net (code "132") (name "unconnected-(U2C-DRAM_D48-PadAC22)") (class "Default")
      (node (ref "U2") (pin "AC22") (pinfunction "DRAM_D48_AC22") (pintype "bidirectional"))
    )
    (net (code "133") (name "unconnected-(U2C-DRAM_D49-PadAE22)") (class "Default")
      (node (ref "U2") (pin "AE22") (pinfunction "DRAM_D49_AE22") (pintype "bidirectional"))
    )
    (net (code "134") (name "unconnected-(U2C-DRAM_D50-PadAE24)") (class "Default")
      (node (ref "U2") (pin "AE24") (pinfunction "DRAM_D50_AE24") (pintype "bidirectional"))
    )
    (net (code "135") (name "unconnected-(U2C-DRAM_D51-PadAC24)") (class "Default")
      (node (ref "U2") (pin "AC24") (pinfunction "DRAM_D51_AC24") (pintype "bidirectional"))
    )
    (net (code "136") (name "unconnected-(U2C-DRAM_D52-PadAB22)") (class "Default")
      (node (ref "U2") (pin "AB22") (pinfunction "DRAM_D52_AB22") (pintype "bidirectional"))
    )
    (net (code "137") (name "unconnected-(U2C-DRAM_D53-PadAC23)") (class "Default")
      (node (ref "U2") (pin "AC23") (pinfunction "DRAM_D53_AC23") (pintype "bidirectional"))
    )
    (net (code "138") (name "unconnected-(U2C-DRAM_D54-PadAD25)") (class "Default")
      (node (ref "U2") (pin "AD25") (pinfunction "DRAM_D54_AD25") (pintype "bidirectional"))
    )
    (net (code "139") (name "unconnected-(U2C-DRAM_D55-PadAC25)") (class "Default")
      (node (ref "U2") (pin "AC25") (pinfunction "DRAM_D55_AC25") (pintype "bidirectional"))
    )
    (net (code "140") (name "unconnected-(U2C-DRAM_D56-PadAB25)") (class "Default")
      (node (ref "U2") (pin "AB25") (pinfunction "DRAM_D56_AB25") (pintype "bidirectional"))
    )
    (net (code "141") (name "unconnected-(U2C-DRAM_D57-PadAA21)") (class "Default")
      (node (ref "U2") (pin "AA21") (pinfunction "DRAM_D57_AA21") (pintype "bidirectional"))
    )
    (net (code "142") (name "unconnected-(U2C-DRAM_D58-PadY25)") (class "Default")
      (node (ref "U2") (pin "Y25") (pinfunction "DRAM_D58_Y25") (pintype "bidirectional"))
    )
    (net (code "143") (name "unconnected-(U2C-DRAM_D59-PadY22)") (class "Default")
      (node (ref "U2") (pin "Y22") (pinfunction "DRAM_D59_Y22") (pintype "bidirectional"))
    )
    (net (code "144") (name "unconnected-(U2C-DRAM_D60-PadAB23)") (class "Default")
      (node (ref "U2") (pin "AB23") (pinfunction "DRAM_D60_AB23") (pintype "bidirectional"))
    )
    (net (code "145") (name "unconnected-(U2C-DRAM_D61-PadAA23)") (class "Default")
      (node (ref "U2") (pin "AA23") (pinfunction "DRAM_D61_AA23") (pintype "bidirectional"))
    )
    (net (code "146") (name "unconnected-(U2C-DRAM_D62-PadY23)") (class "Default")
      (node (ref "U2") (pin "Y23") (pinfunction "DRAM_D62_Y23") (pintype "bidirectional"))
    )
    (net (code "147") (name "unconnected-(U2C-DRAM_D63-PadW25)") (class "Default")
      (node (ref "U2") (pin "W25") (pinfunction "DRAM_D63_W25") (pintype "bidirectional"))
    )
    (net (code "148") (name "unconnected-(U2C-DRAM_DQM4-PadAB18)") (class "Default")
      (node (ref "U2") (pin "AB18") (pinfunction "DRAM_DQM4_AB18") (pintype "output"))
    )
    (net (code "149") (name "unconnected-(U2C-DRAM_DQM5-PadAC20)") (class "Default")
      (node (ref "U2") (pin "AC20") (pinfunction "DRAM_DQM5_AC20") (pintype "output"))
    )
    (net (code "150") (name "unconnected-(U2C-DRAM_DQM6-PadAD24)") (class "Default")
      (node (ref "U2") (pin "AD24") (pinfunction "DRAM_DQM6_AD24") (pintype "output"))
    )
    (net (code "151") (name "unconnected-(U2C-DRAM_DQM7-PadY21)") (class "Default")
      (node (ref "U2") (pin "Y21") (pinfunction "DRAM_DQM7_Y21") (pintype "output"))
    )
    (net (code "152") (name "unconnected-(U2C-DRAM_SDCKE1-PadAA11)") (class "Default")
      (node (ref "U2") (pin "AA11") (pinfunction "DRAM_SDCKE1_AA11") (pintype "output"))
    )
    (net (code "153") (name "unconnected-(U2C-DRAM_SDODT1-PadAB17)") (class "Default")
      (node (ref "U2") (pin "AB17") (pinfunction "DRAM_SDODT1_AB17") (pintype "output"))
    )
    (net (code "154") (name "unconnected-(U2C-DRAM_SDQS4-PadAD18)") (class "Default")
      (node (ref "U2") (pin "AD18") (pinfunction "DRAM_SDQS4_AD18") (pintype "bidirectional"))
    )
    (net (code "155") (name "unconnected-(U2C-DRAM_SDQS5-PadAD20)") (class "Default")
      (node (ref "U2") (pin "AD20") (pinfunction "DRAM_SDQS5_AD20") (pintype "bidirectional"))
    )
    (net (code "156") (name "unconnected-(U2C-DRAM_SDQS6-PadAD23)") (class "Default")
      (node (ref "U2") (pin "AD23") (pinfunction "DRAM_SDQS6_AD23") (pintype "bidirectional"))
    )
    (net (code "157") (name "unconnected-(U2C-DRAM_SDQS7-PadAA25)") (class "Default")
      (node (ref "U2") (pin "AA25") (pinfunction "DRAM_SDQS7_AA25") (pintype "bidirectional"))
    )
    (net (code "158") (name "unconnected-(U2C-~{DRAM_SDQS4}-PadAE18)") (class "Default")
      (node (ref "U2") (pin "AE18") (pinfunction "~{DRAM_SDQS4}_AE18") (pintype "bidirectional"))
    )
    (net (code "159") (name "unconnected-(U2C-~{DRAM_SDQS5}-PadAE20)") (class "Default")
      (node (ref "U2") (pin "AE20") (pinfunction "~{DRAM_SDQS5}_AE20") (pintype "bidirectional"))
    )
    (net (code "160") (name "unconnected-(U2C-~{DRAM_SDQS6}-PadAE23)") (class "Default")
      (node (ref "U2") (pin "AE23") (pinfunction "~{DRAM_SDQS6}_AE23") (pintype "bidirectional"))
    )
    (net (code "161") (name "unconnected-(U2C-~{DRAM_SDQS7}-PadAA24)") (class "Default")
      (node (ref "U2") (pin "AA24") (pinfunction "~{DRAM_SDQS7}_AA24") (pintype "bidirectional"))
    )
    (net (code "162") (name "unconnected-(U3-NC_J1-PadJ1)") (class "Default")
      (node (ref "U3") (pin "J1") (pinfunction "NC_J1_J1") (pintype "passive"))
    )
    (net (code "163") (name "unconnected-(U3-NC_J9-PadJ9)") (class "Default")
      (node (ref "U3") (pin "J9") (pinfunction "NC_J9_J9") (pintype "passive"))
    )
    (net (code "164") (name "unconnected-(U3-NC_L1-PadL1)") (class "Default")
      (node (ref "U3") (pin "L1") (pinfunction "NC_L1_L1") (pintype "passive"))
    )
    (net (code "165") (name "unconnected-(U3-NC_L9-PadL9)") (class "Default")
      (node (ref "U3") (pin "L9") (pinfunction "NC_L9_L9") (pintype "passive"))
    )
    (net (code "166") (name "unconnected-(U4-NC_J1-PadJ1)") (class "Default")
      (node (ref "U4") (pin "J1") (pinfunction "NC_J1_J1") (pintype "passive"))
    )
    (net (code "167") (name "unconnected-(U4-NC_J9-PadJ9)") (class "Default")
      (node (ref "U4") (pin "J9") (pinfunction "NC_J9_J9") (pintype "passive"))
    )
    (net (code "168") (name "unconnected-(U4-NC_L1-PadL1)") (class "Default")
      (node (ref "U4") (pin "L1") (pinfunction "NC_L1_L1") (pintype "passive"))
    )
    (net (code "169") (name "unconnected-(U4-NC_L9-PadL9)") (class "Default")
      (node (ref "U4") (pin "L9") (pinfunction "NC_L9_L9") (pintype "passive"))
    )
  )
)
